# SuperClock_Core_WIFI.net
KiCad netlist of a schematic drawn in Altium Designer
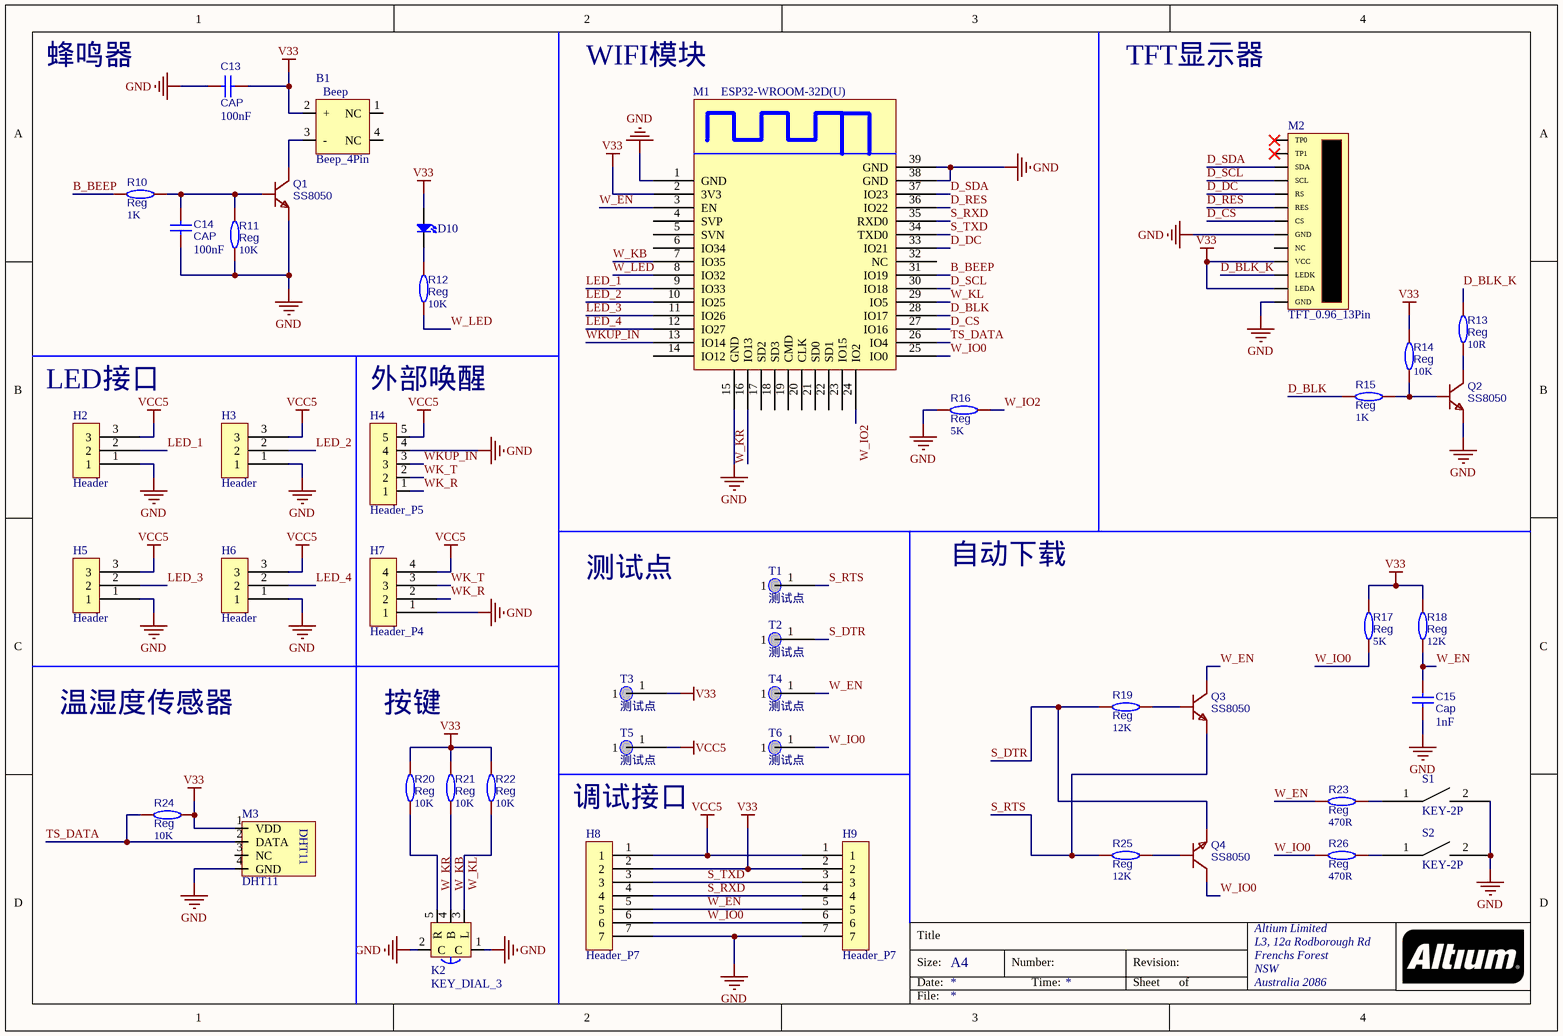
[diagram p0: SuperClock_Core_WIFI.SchDoc]

(export (version "E")
  (design (tool "Eeschema 10.0.6"))
  (components
    (comp (ref "B1")
      (value "Beep_4Pin")
      (footprint "Beep_4Pin_7525")
      (description "4Pin蜂鸣器")
      (libsource (lib "Levent_lib") (part "Beep_4Pin"))
    )
    (comp (ref "C13")
      (value "CAP")
      (footprint "C0603")
      (description "Cap")
      (fields
        (field (name "BOM_SUPPLIER PART") "C302008")
        (field (name "BOM_MANUFACTURER PART") "0603B103K101CT")
        (field (name "ALTIUM_VALUE") "100nF")
        (field (name "CONTRIBUTOR") "LCSC")
      )
      (libsource (lib "Levent_lib") (part "CAP"))
    )
    (comp (ref "C14")
      (value "CAP")
      (footprint "C0603")
      (description "Cap")
      (fields
        (field (name "BOM_SUPPLIER PART") "C302008")
        (field (name "BOM_MANUFACTURER PART") "0603B103K101CT")
        (field (name "ALTIUM_VALUE") "100nF")
        (field (name "CONTRIBUTOR") "LCSC")
      )
      (libsource (lib "Levent_lib") (part "CAP"))
    )
    (comp (ref "C15")
      (value "Cap")
      (footprint "C0603")
      (fields
        (field (name "BOM_SUPPLIER PART") "C302008")
        (field (name "BOM_MANUFACTURER PART") "0603B103K101CT")
        (field (name "ALTIUM_VALUE") "1nF")
        (field (name "CONTRIBUTOR") "LCSC")
      )
      (libsource (lib "Levent_lib") (part "CAP"))
    )
    (comp (ref "D10")
      (value "LED")
      (footprint "LED0603")
      (fields (field (name "PUBLISHER") "Altium Limited"))
      (libsource (lib "Levent_lib") (part "LED0"))
    )
    (comp (ref "H2")
      (value "Header")
      (footprint "H_2.54_P3")
      (description "3Pin接口")
      (libsource (lib "Levent_lib") (part "Header_P3"))
    )
    (comp (ref "H3")
      (value "Header")
      (footprint "H_2.54_P3")
      (description "3Pin接口")
      (libsource (lib "Levent_lib") (part "Header_P3"))
    )
    (comp (ref "H4")
      (value "Header_P5")
      (footprint "H_1.27_P5")
      (description "5Pin排针")
      (libsource (lib "Levent_lib") (part "Header_P5"))
    )
    (comp (ref "H5")
      (value "Header")
      (footprint "H_2.54_P3")
      (description "3Pin接口")
      (libsource (lib "Levent_lib") (part "Header_P3"))
    )
    (comp (ref "H6")
      (value "Header")
      (footprint "H_2.54_P3")
      (description "3Pin接口")
      (libsource (lib "Levent_lib") (part "Header_P3"))
    )
    (comp (ref "H7")
      (value "Header_P4")
      (footprint "H_2.54_P4")
      (description "4Pin排针")
      (libsource (lib "Levent_lib") (part "Header_P4"))
    )
    (comp (ref "H8")
      (value "Header_P7")
      (footprint "H_2.54_P7")
      (description "7Pin排针")
      (libsource (lib "") (part "Header_P7_1"))
    )
    (comp (ref "H9")
      (value "Header_P7")
      (footprint "H_2.54_P7")
      (description "7Pin排针")
      (libsource (lib "Levent_lib") (part "Header_P7"))
    )
    (comp (ref "K2")
      (value "KEY_DIAL_3")
      (footprint "KEY_DIAL_3")
      (description "3向拨轮开关")
      (libsource (lib "Levent_lib") (part "KEY_DIAL_3"))
    )
    (comp (ref "M1")
      (value "ESP32-WROOM-32D(U)")
      (footprint "ESP32-WROOM-32D")
      (libsource (lib "Levent_lib") (part "ESP32-WROOM-32D(U)"))
    )
    (comp (ref "M2")
      (value "TFT_0.96_13Pin")
      (footprint "TFT_0.96_13Pin")
      (description "ST7735_TFT")
      (libsource (lib "Levent_lib") (part "TFT_0.96_13Pin"))
    )
    (comp (ref "M3")
      (value "DHT11")
      (footprint "SENSOR-TH_DHT11-HOR")
      (description "温湿度传感器")
      (libsource (lib "Levent_lib") (part "DHT11"))
    )
    (comp (ref "Q1")
      (value "SS8050")
      (footprint "SOT-23-3")
      (description "NPN")
      (fields (field (name "BOM_SUPPLIER PART") "C541705") (field (name "CONTRIBUTOR") "LCSC"))
      (libsource (lib "Levent_lib") (part "SS8050"))
    )
    (comp (ref "Q2")
      (value "SS8050")
      (footprint "SOT-23-3")
      (description "NPN")
      (fields (field (name "BOM_SUPPLIER PART") "C541705") (field (name "CONTRIBUTOR") "LCSC"))
      (libsource (lib "Levent_lib") (part "SS8050"))
    )
    (comp (ref "Q3")
      (value "SS8050")
      (footprint "SOT-23-3")
      (description "NPN")
      (fields (field (name "BOM_SUPPLIER PART") "C541705") (field (name "CONTRIBUTOR") "LCSC"))
      (libsource (lib "Levent_lib") (part "SS8050"))
    )
    (comp (ref "Q4")
      (value "SS8050")
      (footprint "SOT-23-3")
      (description "NPN")
      (fields (field (name "BOM_SUPPLIER PART") "C541705") (field (name "CONTRIBUTOR") "LCSC"))
      (libsource (lib "Levent_lib") (part "SS8050"))
    )
    (comp (ref "R10")
      (value "Reg")
      (footprint "R0603")
      (description "电阻")
      (fields
        (field (name "BOM_SUPPLIER PART") "C465721")
        (field (name "BOM_MANUFACTURER PART") "AR03BTCX1002A")
        (field (name "ALTIUM_VALUE") "1K")
        (field (name "CONTRIBUTOR") "LCSC")
      )
      (libsource (lib "Levent_lib") (part "Res"))
    )
    (comp (ref "R11")
      (value "Reg")
      (footprint "R0603")
      (description "电阻")
      (fields
        (field (name "BOM_SUPPLIER PART") "C465721")
        (field (name "BOM_MANUFACTURER PART") "AR03BTCX1002A")
        (field (name "ALTIUM_VALUE") "10K")
        (field (name "CONTRIBUTOR") "LCSC")
      )
      (libsource (lib "Levent_lib") (part "Res"))
    )
    (comp (ref "R12")
      (value "Reg")
      (footprint "R0603")
      (description "电阻")
      (fields
        (field (name "BOM_SUPPLIER PART") "C465721")
        (field (name "BOM_MANUFACTURER PART") "AR03BTCX1002A")
        (field (name "ALTIUM_VALUE") "10K")
        (field (name "CONTRIBUTOR") "LCSC")
      )
      (libsource (lib "Levent_lib") (part "Res"))
    )
    (comp (ref "R13")
      (value "Reg")
      (footprint "R0603")
      (description "电阻")
      (fields
        (field (name "BOM_SUPPLIER PART") "C465721")
        (field (name "BOM_MANUFACTURER PART") "AR03BTCX1002A")
        (field (name "ALTIUM_VALUE") "10R")
        (field (name "CONTRIBUTOR") "LCSC")
      )
      (libsource (lib "Levent_lib") (part "Res"))
    )
    (comp (ref "R14")
      (value "Reg")
      (footprint "R0603")
      (description "电阻")
      (fields
        (field (name "BOM_SUPPLIER PART") "C465721")
        (field (name "BOM_MANUFACTURER PART") "AR03BTCX1002A")
        (field (name "ALTIUM_VALUE") "10K")
        (field (name "CONTRIBUTOR") "LCSC")
      )
      (libsource (lib "Levent_lib") (part "Res"))
    )
    (comp (ref "R15")
      (value "Reg")
      (footprint "R0603")
      (description "电阻")
      (fields
        (field (name "BOM_SUPPLIER PART") "C465721")
        (field (name "BOM_MANUFACTURER PART") "AR03BTCX1002A")
        (field (name "ALTIUM_VALUE") "1K")
        (field (name "CONTRIBUTOR") "LCSC")
      )
      (libsource (lib "Levent_lib") (part "Res"))
    )
    (comp (ref "R16")
      (value "Reg")
      (footprint "R0603")
      (description "电阻")
      (fields
        (field (name "BOM_SUPPLIER PART") "C465721")
        (field (name "BOM_MANUFACTURER PART") "AR03BTCX1002A")
        (field (name "ALTIUM_VALUE") "5K")
        (field (name "CONTRIBUTOR") "LCSC")
      )
      (libsource (lib "Levent_lib") (part "Res"))
    )
    (comp (ref "R17")
      (value "Reg")
      (footprint "R0603")
      (description "电阻")
      (fields
        (field (name "BOM_SUPPLIER PART") "C465721")
        (field (name "BOM_MANUFACTURER PART") "AR03BTCX1002A")
        (field (name "ALTIUM_VALUE") "5K")
        (field (name "CONTRIBUTOR") "LCSC")
      )
      (libsource (lib "Levent_lib") (part "Res"))
    )
    (comp (ref "R18")
      (value "Reg")
      (footprint "R0603")
      (description "电阻")
      (fields
        (field (name "BOM_SUPPLIER PART") "C465721")
        (field (name "BOM_MANUFACTURER PART") "AR03BTCX1002A")
        (field (name "ALTIUM_VALUE") "12K")
        (field (name "CONTRIBUTOR") "LCSC")
      )
      (libsource (lib "Levent_lib") (part "Res"))
    )
    (comp (ref "R19")
      (value "Reg")
      (footprint "R0603")
      (description "电阻")
      (fields
        (field (name "BOM_SUPPLIER PART") "C465721")
        (field (name "BOM_MANUFACTURER PART") "AR03BTCX1002A")
        (field (name "ALTIUM_VALUE") "12K")
        (field (name "CONTRIBUTOR") "LCSC")
      )
      (libsource (lib "Levent_lib") (part "Res"))
    )
    (comp (ref "R20")
      (value "Reg")
      (footprint "R0603")
      (description "电阻")
      (fields
        (field (name "BOM_SUPPLIER PART") "C465721")
        (field (name "BOM_MANUFACTURER PART") "AR03BTCX1002A")
        (field (name "ALTIUM_VALUE") "10K")
        (field (name "CONTRIBUTOR") "LCSC")
      )
      (libsource (lib "Levent_lib") (part "Res"))
    )
    (comp (ref "R21")
      (value "Reg")
      (footprint "R0603")
      (description "电阻")
      (fields
        (field (name "BOM_SUPPLIER PART") "C465721")
        (field (name "BOM_MANUFACTURER PART") "AR03BTCX1002A")
        (field (name "ALTIUM_VALUE") "10K")
        (field (name "CONTRIBUTOR") "LCSC")
      )
      (libsource (lib "Levent_lib") (part "Res"))
    )
    (comp (ref "R22")
      (value "Reg")
      (footprint "R0603")
      (description "电阻")
      (fields
        (field (name "BOM_SUPPLIER PART") "C465721")
        (field (name "BOM_MANUFACTURER PART") "AR03BTCX1002A")
        (field (name "ALTIUM_VALUE") "10K")
        (field (name "CONTRIBUTOR") "LCSC")
      )
      (libsource (lib "Levent_lib") (part "Res"))
    )
    (comp (ref "R23")
      (value "Reg")
      (footprint "R0603")
      (description "电阻")
      (fields
        (field (name "BOM_SUPPLIER PART") "C465721")
        (field (name "BOM_MANUFACTURER PART") "AR03BTCX1002A")
        (field (name "ALTIUM_VALUE") "470R")
        (field (name "CONTRIBUTOR") "LCSC")
      )
      (libsource (lib "Levent_lib") (part "Res"))
    )
    (comp (ref "R24")
      (value "Reg")
      (footprint "R0603")
      (description "电阻")
      (fields
        (field (name "BOM_SUPPLIER PART") "C465721")
        (field (name "BOM_MANUFACTURER PART") "AR03BTCX1002A")
        (field (name "ALTIUM_VALUE") "10K")
        (field (name "CONTRIBUTOR") "LCSC")
      )
      (libsource (lib "Levent_lib") (part "Res"))
    )
    (comp (ref "R25")
      (value "Reg")
      (footprint "R0603")
      (description "电阻")
      (fields
        (field (name "BOM_SUPPLIER PART") "C465721")
        (field (name "BOM_MANUFACTURER PART") "AR03BTCX1002A")
        (field (name "ALTIUM_VALUE") "12K")
        (field (name "CONTRIBUTOR") "LCSC")
      )
      (libsource (lib "Levent_lib") (part "Res"))
    )
    (comp (ref "R26")
      (value "Reg")
      (footprint "R0603")
      (description "电阻")
      (fields
        (field (name "BOM_SUPPLIER PART") "C465721")
        (field (name "BOM_MANUFACTURER PART") "AR03BTCX1002A")
        (field (name "ALTIUM_VALUE") "470R")
        (field (name "CONTRIBUTOR") "LCSC")
      )
      (libsource (lib "Levent_lib") (part "Res"))
    )
    (comp (ref "S1")
      (value "KEY-2P")
      (footprint "KEY_SOT_P2")
      (description "KEY-2Pp")
      (libsource (lib "Levent_lib") (part "KEY_2P"))
    )
    (comp (ref "S2")
      (value "KEY-2P")
      (footprint "KEY_SOT_P2")
      (description "KEY-2Pp")
      (libsource (lib "Levent_lib") (part "KEY_2P"))
    )
    (comp (ref "T1")
      (value "测试点")
      (footprint "TEST_POINT")
      (libsource (lib "Levent_lib") (part "TEST_POINT"))
    )
    (comp (ref "T2")
      (value "测试点")
      (footprint "TEST_POINT")
      (libsource (lib "Levent_lib") (part "TEST_POINT"))
    )
    (comp (ref "T3")
      (value "测试点")
      (footprint "TEST_POINT")
      (libsource (lib "Levent_lib") (part "TEST_POINT"))
    )
    (comp (ref "T4")
      (value "测试点")
      (footprint "TEST_POINT")
      (libsource (lib "Levent_lib") (part "TEST_POINT"))
    )
    (comp (ref "T5")
      (value "测试点")
      (footprint "TEST_POINT")
      (libsource (lib "Levent_lib") (part "TEST_POINT"))
    )
    (comp (ref "T6")
      (value "测试点")
      (footprint "TEST_POINT")
      (libsource (lib "Levent_lib") (part "TEST_POINT"))
    )
  )
  (nets
    (net (code "1") (name "/B_BEEP") (class "Default")
      (node (ref "M1") (pin "31") (pinfunction "IO19_31") (pintype "passive"))
      (node (ref "R10") (pin "2") (pinfunction "2_2") (pintype "passive"))
    )
    (net (code "2") (name "/D_BLK") (class "Default")
      (node (ref "M1") (pin "28") (pinfunction "IO17_28") (pintype "passive"))
      (node (ref "R15") (pin "2") (pinfunction "2_2") (pintype "passive"))
    )
    (net (code "3") (name "/D_BLK_K") (class "Default")
      (node (ref "M2") (pin "11") (pinfunction "LEDK_11") (pintype "passive"))
      (node (ref "R13") (pin "2") (pinfunction "2_2") (pintype "passive"))
    )
    (net (code "4") (name "/D_CS") (class "Default")
      (node (ref "M1") (pin "27") (pinfunction "IO16_27") (pintype "passive"))
      (node (ref "M2") (pin "7") (pinfunction "CS_7") (pintype "passive"))
    )
    (net (code "5") (name "/D_DC") (class "Default")
      (node (ref "M1") (pin "33") (pinfunction "IO21_33") (pintype "passive"))
      (node (ref "M2") (pin "5") (pinfunction "RS_5") (pintype "passive"))
    )
    (net (code "6") (name "/D_RES") (class "Default")
      (node (ref "M1") (pin "36") (pinfunction "IO22_36") (pintype "passive"))
      (node (ref "M2") (pin "6") (pinfunction "RES_6") (pintype "passive"))
    )
    (net (code "7") (name "/D_SCL") (class "Default")
      (node (ref "M1") (pin "30") (pinfunction "IO18_30") (pintype "passive"))
      (node (ref "M2") (pin "4") (pinfunction "SCL_4") (pintype "passive"))
    )
    (net (code "8") (name "/D_SDA") (class "Default")
      (node (ref "M1") (pin "37") (pinfunction "IO23_37") (pintype "passive"))
      (node (ref "M2") (pin "3") (pinfunction "SDA_3") (pintype "passive"))
    )
    (net (code "9") (name "/LED_1") (class "Default")
      (node (ref "H2") (pin "2") (pinfunction "2_2") (pintype "passive"))
      (node (ref "M1") (pin "9") (pinfunction "IO33_9") (pintype "passive"))
    )
    (net (code "10") (name "/LED_2") (class "Default")
      (node (ref "H3") (pin "2") (pinfunction "2_2") (pintype "passive"))
      (node (ref "M1") (pin "10") (pinfunction "IO25_10") (pintype "passive"))
    )
    (net (code "11") (name "/LED_3") (class "Default")
      (node (ref "H5") (pin "2") (pinfunction "2_2") (pintype "passive"))
      (node (ref "M1") (pin "11") (pinfunction "IO26_11") (pintype "passive"))
    )
    (net (code "12") (name "/LED_4") (class "Default")
      (node (ref "H6") (pin "2") (pinfunction "2_2") (pintype "passive"))
      (node (ref "M1") (pin "12") (pinfunction "IO27_12") (pintype "passive"))
    )
    (net (code "13") (name "/S_DTR") (class "Default")
      (node (ref "Q4") (pin "2") (pinfunction "E_2") (pintype "passive"))
      (node (ref "R19") (pin "2") (pinfunction "2_2") (pintype "passive"))
      (node (ref "T2") (pin "1") (pinfunction "1_1") (pintype "passive"))
    )
    (net (code "14") (name "/S_RTS") (class "Default")
      (node (ref "Q3") (pin "2") (pinfunction "E_2") (pintype "passive"))
      (node (ref "R25") (pin "2") (pinfunction "2_2") (pintype "passive"))
      (node (ref "T1") (pin "1") (pinfunction "1_1") (pintype "passive"))
    )
    (net (code "15") (name "/S_RXD") (class "Default")
      (node (ref "H8") (pin "4") (pinfunction "4_4") (pintype "passive"))
      (node (ref "H9") (pin "4") (pinfunction "4_4") (pintype "passive"))
      (node (ref "M1") (pin "35") (pinfunction "RXD0_35") (pintype "passive"))
    )
    (net (code "16") (name "/S_TXD") (class "Default")
      (node (ref "H8") (pin "3") (pinfunction "3_3") (pintype "passive"))
      (node (ref "H9") (pin "3") (pinfunction "3_3") (pintype "passive"))
      (node (ref "M1") (pin "34") (pinfunction "TXD0_34") (pintype "passive"))
    )
    (net (code "17") (name "/TS_DATA") (class "Default")
      (node (ref "M1") (pin "26") (pinfunction "IO4_26") (pintype "passive"))
      (node (ref "M3") (pin "2") (pinfunction "DATA_2") (pintype "passive"))
      (node (ref "R24") (pin "2") (pinfunction "2_2") (pintype "passive"))
    )
    (net (code "18") (name "/WKUP_IN") (class "Default")
      (node (ref "H4") (pin "3") (pinfunction "3_3") (pintype "passive"))
      (node (ref "M1") (pin "13") (pinfunction "IO14_13") (pintype "passive"))
    )
    (net (code "19") (name "/WK_R") (class "Default")
      (node (ref "H4") (pin "1") (pinfunction "1_1") (pintype "passive"))
      (node (ref "H7") (pin "2") (pinfunction "2_2") (pintype "passive"))
    )
    (net (code "20") (name "/WK_T") (class "Default")
      (node (ref "H4") (pin "2") (pinfunction "2_2") (pintype "passive"))
      (node (ref "H7") (pin "3") (pinfunction "3_3") (pintype "passive"))
    )
    (net (code "21") (name "/W_EN") (class "Default")
      (node (ref "C15") (pin "1") (pinfunction "1_1") (pintype "passive"))
      (node (ref "H8") (pin "5") (pinfunction "5_5") (pintype "passive"))
      (node (ref "H9") (pin "5") (pinfunction "5_5") (pintype "passive"))
      (node (ref "M1") (pin "3") (pinfunction "EN_3") (pintype "passive"))
      (node (ref "Q3") (pin "3") (pinfunction "C_3") (pintype "passive"))
      (node (ref "R18") (pin "1") (pinfunction "1_1") (pintype "passive"))
      (node (ref "R23") (pin "2") (pinfunction "2_2") (pintype "passive"))
      (node (ref "T4") (pin "1") (pinfunction "1_1") (pintype "passive"))
    )
    (net (code "22") (name "/W_IO0") (class "Default")
      (node (ref "H8") (pin "6") (pinfunction "6_6") (pintype "passive"))
      (node (ref "H9") (pin "6") (pinfunction "6_6") (pintype "passive"))
      (node (ref "M1") (pin "25") (pinfunction "IO0_25") (pintype "passive"))
      (node (ref "Q4") (pin "3") (pinfunction "C_3") (pintype "passive"))
      (node (ref "R17") (pin "1") (pinfunction "1_1") (pintype "passive"))
      (node (ref "R26") (pin "2") (pinfunction "2_2") (pintype "passive"))
      (node (ref "T6") (pin "1") (pinfunction "1_1") (pintype "passive"))
    )
    (net (code "23") (name "/W_IO2") (class "Default")
      (node (ref "M1") (pin "24") (pinfunction "IO2_24") (pintype "passive"))
      (node (ref "R16") (pin "1") (pinfunction "1_1") (pintype "passive"))
    )
    (net (code "24") (name "/W_KB") (class "Default")
      (node (ref "K2") (pin "4") (pinfunction "B_4") (pintype "passive"))
      (node (ref "M1") (pin "7") (pinfunction "IO35_7") (pintype "passive"))
      (node (ref "R21") (pin "2") (pinfunction "2_2") (pintype "passive"))
    )
    (net (code "25") (name "/W_KL") (class "Default")
      (node (ref "K2") (pin "3") (pinfunction "L_3") (pintype "passive"))
      (node (ref "M1") (pin "29") (pinfunction "IO5_29") (pintype "passive"))
      (node (ref "R22") (pin "2") (pinfunction "2_2") (pintype "passive"))
    )
    (net (code "26") (name "/W_KR") (class "Default")
      (node (ref "K2") (pin "5") (pinfunction "R_5") (pintype "passive"))
      (node (ref "M1") (pin "16") (pinfunction "IO13_16") (pintype "passive"))
      (node (ref "R20") (pin "2") (pinfunction "2_2") (pintype "passive"))
    )
    (net (code "27") (name "/W_LED") (class "Default")
      (node (ref "M1") (pin "8") (pinfunction "IO32_8") (pintype "passive"))
      (node (ref "R12") (pin "1") (pinfunction "1_1") (pintype "passive"))
    )
    (net (code "28") (name "GND") (class "Default")
      (node (ref "C13") (pin "1") (pinfunction "1_1") (pintype "passive"))
      (node (ref "C14") (pin "2") (pinfunction "2_2") (pintype "passive"))
      (node (ref "C15") (pin "2") (pinfunction "2_2") (pintype "passive"))
      (node (ref "H2") (pin "1") (pinfunction "1_1") (pintype "passive"))
      (node (ref "H3") (pin "1") (pinfunction "1_1") (pintype "passive"))
      (node (ref "H4") (pin "4") (pinfunction "4_4") (pintype "passive"))
      (node (ref "H5") (pin "1") (pinfunction "1_1") (pintype "passive"))
      (node (ref "H6") (pin "1") (pinfunction "1_1") (pintype "passive"))
      (node (ref "H7") (pin "1") (pinfunction "1_1") (pintype "passive"))
      (node (ref "H8") (pin "7") (pinfunction "7_7") (pintype "passive"))
      (node (ref "H9") (pin "7") (pinfunction "7_7") (pintype "passive"))
      (node (ref "K2") (pin "1") (pinfunction "C_1") (pintype "passive"))
      (node (ref "K2") (pin "2") (pinfunction "C_2") (pintype "passive"))
      (node (ref "M1") (pin "1") (pinfunction "GND_1") (pintype "passive"))
      (node (ref "M1") (pin "15") (pinfunction "GND_15") (pintype "passive"))
      (node (ref "M1") (pin "38") (pinfunction "GND_38") (pintype "passive"))
      (node (ref "M1") (pin "39") (pinfunction "GND_39") (pintype "passive"))
      (node (ref "M2") (pin "13") (pinfunction "GND_13") (pintype "passive"))
      (node (ref "M2") (pin "8") (pinfunction "GND_8") (pintype "passive"))
      (node (ref "M3") (pin "4") (pinfunction "GND_4") (pintype "passive"))
      (node (ref "Q1") (pin "2") (pinfunction "E_2") (pintype "passive"))
      (node (ref "Q2") (pin "2") (pinfunction "E_2") (pintype "passive"))
      (node (ref "R11") (pin "2") (pinfunction "2_2") (pintype "passive"))
      (node (ref "R16") (pin "2") (pinfunction "2_2") (pintype "passive"))
      (node (ref "S1") (pin "2") (pinfunction "2_2") (pintype "passive"))
      (node (ref "S2") (pin "2") (pinfunction "2_2") (pintype "passive"))
    )
    (net (code "29") (name "Net-(B1--)") (class "Default")
      (node (ref "B1") (pin "3") (pinfunction "-_3") (pintype "passive"))
      (node (ref "Q1") (pin "3") (pinfunction "C_3") (pintype "passive"))
    )
    (net (code "30") (name "Net-(D10-K)") (class "Default")
      (node (ref "D10") (pin "1") (pinfunction "K_1") (pintype "passive"))
      (node (ref "R12") (pin "2") (pinfunction "2_2") (pintype "passive"))
    )
    (net (code "31") (name "Net-(Q1-B)") (class "Default")
      (node (ref "C14") (pin "1") (pinfunction "1_1") (pintype "passive"))
      (node (ref "Q1") (pin "1") (pinfunction "B_1") (pintype "passive"))
      (node (ref "R10") (pin "1") (pinfunction "1_1") (pintype "passive"))
      (node (ref "R11") (pin "1") (pinfunction "1_1") (pintype "passive"))
    )
    (net (code "32") (name "Net-(Q2-B)") (class "Default")
      (node (ref "Q2") (pin "1") (pinfunction "B_1") (pintype "passive"))
      (node (ref "R14") (pin "1") (pinfunction "1_1") (pintype "passive"))
      (node (ref "R15") (pin "1") (pinfunction "1_1") (pintype "passive"))
    )
    (net (code "33") (name "Net-(Q2-C)") (class "Default")
      (node (ref "Q2") (pin "3") (pinfunction "C_3") (pintype "passive"))
      (node (ref "R13") (pin "1") (pinfunction "1_1") (pintype "passive"))
    )
    (net (code "34") (name "Net-(Q3-B)") (class "Default")
      (node (ref "Q3") (pin "1") (pinfunction "B_1") (pintype "passive"))
      (node (ref "R19") (pin "1") (pinfunction "1_1") (pintype "passive"))
    )
    (net (code "35") (name "Net-(Q4-B)") (class "Default")
      (node (ref "Q4") (pin "1") (pinfunction "B_1") (pintype "passive"))
      (node (ref "R25") (pin "1") (pinfunction "1_1") (pintype "passive"))
    )
    (net (code "36") (name "Net-(R23-Pad1)") (class "Default")
      (node (ref "R23") (pin "1") (pinfunction "1_1") (pintype "passive"))
      (node (ref "S1") (pin "1") (pinfunction "1_1") (pintype "passive"))
    )
    (net (code "37") (name "Net-(R26-Pad1)") (class "Default")
      (node (ref "R26") (pin "1") (pinfunction "1_1") (pintype "passive"))
      (node (ref "S2") (pin "1") (pinfunction "1_1") (pintype "passive"))
    )
    (net (code "38") (name "V33") (class "Default")
      (node (ref "B1") (pin "2") (pinfunction "+_2") (pintype "passive"))
      (node (ref "C13") (pin "2") (pinfunction "2_2") (pintype "passive"))
      (node (ref "D10") (pin "2") (pinfunction "A_2") (pintype "passive"))
      (node (ref "H8") (pin "2") (pinfunction "2_2") (pintype "passive"))
      (node (ref "H9") (pin "2") (pinfunction "2_2") (pintype "passive"))
      (node (ref "M1") (pin "2") (pinfunction "3V3_2") (pintype "passive"))
      (node (ref "M2") (pin "10") (pinfunction "VCC_10") (pintype "passive"))
      (node (ref "M2") (pin "12") (pinfunction "LEDA_12") (pintype "passive"))
      (node (ref "M3") (pin "1") (pinfunction "VDD_1") (pintype "passive"))
      (node (ref "R14") (pin "2") (pinfunction "2_2") (pintype "passive"))
      (node (ref "R17") (pin "2") (pinfunction "2_2") (pintype "passive"))
      (node (ref "R18") (pin "2") (pinfunction "2_2") (pintype "passive"))
      (node (ref "R20") (pin "1") (pinfunction "1_1") (pintype "passive"))
      (node (ref "R21") (pin "1") (pinfunction "1_1") (pintype "passive"))
      (node (ref "R22") (pin "1") (pinfunction "1_1") (pintype "passive"))
      (node (ref "R24") (pin "1") (pinfunction "1_1") (pintype "passive"))
      (node (ref "T3") (pin "1") (pinfunction "1_1") (pintype "passive"))
    )
    (net (code "39") (name "VCC5") (class "Default")
      (node (ref "H2") (pin "3") (pinfunction "3_3") (pintype "passive"))
      (node (ref "H3") (pin "3") (pinfunction "3_3") (pintype "passive"))
      (node (ref "H4") (pin "5") (pinfunction "5_5") (pintype "passive"))
      (node (ref "H5") (pin "3") (pinfunction "3_3") (pintype "passive"))
      (node (ref "H6") (pin "3") (pinfunction "3_3") (pintype "passive"))
      (node (ref "H7") (pin "4") (pinfunction "4_4") (pintype "passive"))
      (node (ref "H8") (pin "1") (pinfunction "1_1") (pintype "passive"))
      (node (ref "H9") (pin "1") (pinfunction "1_1") (pintype "passive"))
      (node (ref "T5") (pin "1") (pinfunction "1_1") (pintype "passive"))
    )
    (net (code "40") (name "unconnected-(B1-NC-Pad1)") (class "Default")
      (node (ref "B1") (pin "1") (pinfunction "NC_1") (pintype "passive"))
    )
    (net (code "41") (name "unconnected-(B1-NC-Pad4)") (class "Default")
      (node (ref "B1") (pin "4") (pinfunction "NC_4") (pintype "passive"))
    )
    (net (code "42") (name "unconnected-(M1-CLK-Pad20)") (class "Default")
      (node (ref "M1") (pin "20") (pinfunction "CLK_20") (pintype "passive"))
    )
    (net (code "43") (name "unconnected-(M1-CMD-Pad19)") (class "Default")
      (node (ref "M1") (pin "19") (pinfunction "CMD_19") (pintype "passive"))
    )
    (net (code "44") (name "unconnected-(M1-IO12-Pad14)") (class "Default")
      (node (ref "M1") (pin "14") (pinfunction "IO12_14") (pintype "passive"))
    )
    (net (code "45") (name "unconnected-(M1-IO15-Pad23)") (class "Default")
      (node (ref "M1") (pin "23") (pinfunction "IO15_23") (pintype "passive"))
    )
    (net (code "46") (name "unconnected-(M1-IO34-Pad6)") (class "Default")
      (node (ref "M1") (pin "6") (pinfunction "IO34_6") (pintype "passive"))
    )
    (net (code "47") (name "unconnected-(M1-NC-Pad32)") (class "Default")
      (node (ref "M1") (pin "32") (pinfunction "NC_32") (pintype "passive"))
    )
    (net (code "48") (name "unconnected-(M1-SD0-Pad21)") (class "Default")
      (node (ref "M1") (pin "21") (pinfunction "SD0_21") (pintype "passive"))
    )
    (net (code "49") (name "unconnected-(M1-SD1-Pad22)") (class "Default")
      (node (ref "M1") (pin "22") (pinfunction "SD1_22") (pintype "passive"))
    )
    (net (code "50") (name "unconnected-(M1-SD2-Pad17)") (class "Default")
      (node (ref "M1") (pin "17") (pinfunction "SD2_17") (pintype "passive"))
    )
    (net (code "51") (name "unconnected-(M1-SD3-Pad18)") (class "Default")
      (node (ref "M1") (pin "18") (pinfunction "SD3_18") (pintype "passive"))
    )
    (net (code "52") (name "unconnected-(M1-SVN-Pad5)") (class "Default")
      (node (ref "M1") (pin "5") (pinfunction "SVN_5") (pintype "passive"))
    )
    (net (code "53") (name "unconnected-(M1-SVP-Pad4)") (class "Default")
      (node (ref "M1") (pin "4") (pinfunction "SVP_4") (pintype "passive"))
    )
    (net (code "54") (name "unconnected-(M2-NC-Pad9)") (class "Default")
      (node (ref "M2") (pin "9") (pinfunction "NC_9") (pintype "passive"))
    )
    (net (code "55") (name "unconnected-(M2-TP0-Pad1)") (class "Default")
      (node (ref "M2") (pin "1") (pinfunction "TP0_1") (pintype "passive+no_connect"))
    )
    (net (code "56") (name "unconnected-(M2-TP1-Pad2)") (class "Default")
      (node (ref "M2") (pin "2") (pinfunction "TP1_2") (pintype "passive+no_connect"))
    )
    (net (code "57") (name "unconnected-(M3-NC-Pad3)") (class "Default")
      (node (ref "M3") (pin "3") (pinfunction "NC_3") (pintype "passive"))
    )
  )
)
